# heaters-sensors.net
KiCad netlist of a schematic drawn in Altium Designer
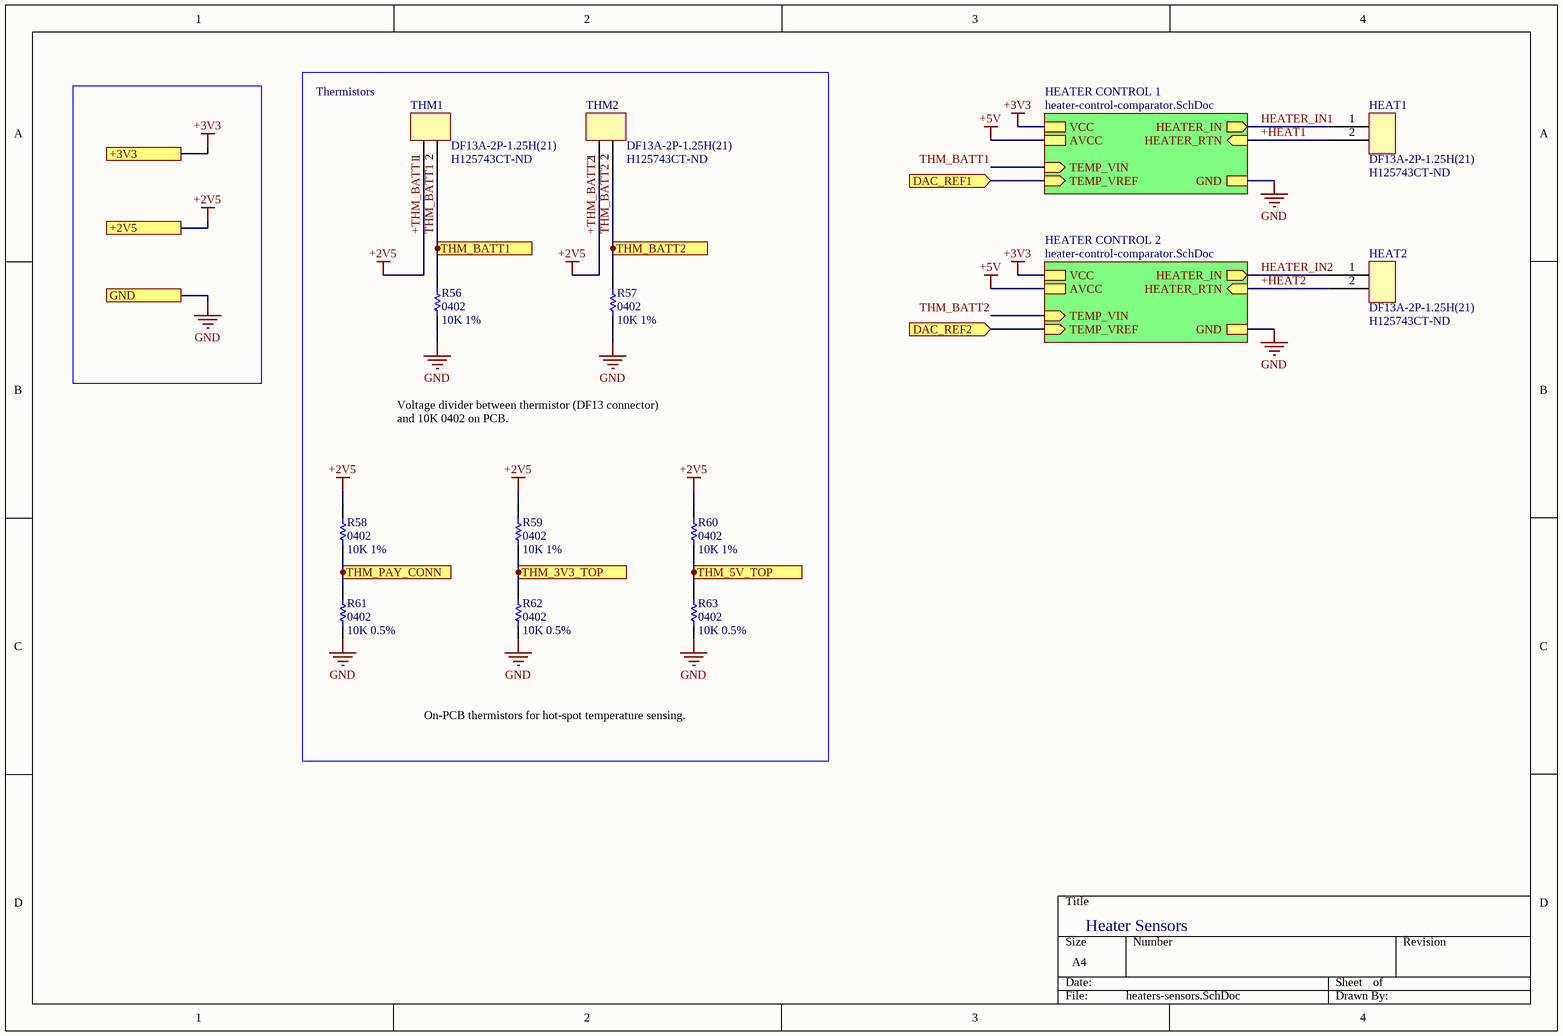
[diagram p0: heaters-sensors.SchDoc]

(export (version "E")
  (design (tool "Eeschema 10.0.6"))
  (components
    (comp (ref "HEAT1")
      (value "DF13A-2P-1.25H(21)")
      (footprint "DF13A-2P-1.25H(21)")
      (description "2 pos DF13 right angle surface mount connector")
      (fields (field (name "SUPPLIER PART NUMBER 1") "H125743CT-ND"))
      (libsource (lib "") (part "DF13A-2P-1.25H(21)_1"))
    )
    (comp (ref "HEAT2")
      (value "DF13A-2P-1.25H(21)")
      (footprint "DF13A-2P-1.25H(21)")
      (description "2 pos DF13 right angle surface mount connector")
      (fields (field (name "SUPPLIER PART NUMBER 1") "H125743CT-ND"))
      (libsource (lib "") (part "DF13A-2P-1.25H(21)_1"))
    )
    (comp (ref "R56")
      (value "0402")
      (footprint "RES0402R")
      (description "0402 resistor")
      (fields (field (name "ALTIUM_VALUE") "10K 1%"))
      (libsource (lib "heron-general") (part "RES0402"))
    )
    (comp (ref "R57")
      (value "0402")
      (footprint "RES0402R")
      (description "0402 resistor")
      (fields (field (name "ALTIUM_VALUE") "10K 1%"))
      (libsource (lib "heron-general") (part "RES0402"))
    )
    (comp (ref "R58")
      (value "0402")
      (footprint "RES0402R")
      (description "0402 resistor")
      (fields (field (name "ALTIUM_VALUE") "10K 1%"))
      (libsource (lib "heron-general") (part "RES0402"))
    )
    (comp (ref "R59")
      (value "0402")
      (footprint "RES0402R")
      (description "0402 resistor")
      (fields (field (name "ALTIUM_VALUE") "10K 1%"))
      (libsource (lib "heron-general") (part "RES0402"))
    )
    (comp (ref "R60")
      (value "0402")
      (footprint "RES0402R")
      (description "0402 resistor")
      (fields (field (name "ALTIUM_VALUE") "10K 1%"))
      (libsource (lib "heron-general") (part "RES0402"))
    )
    (comp (ref "R61")
      (value "0402")
      (footprint "RES0402R")
      (description "0402 thermistor")
      (fields (field (name "ALTIUM_VALUE") "10K 0.5%"))
      (libsource (lib "heron-general") (part "RES0402"))
    )
    (comp (ref "R62")
      (value "0402")
      (footprint "RES0402R")
      (description "0402 thermistor")
      (fields (field (name "ALTIUM_VALUE") "10K 0.5%"))
      (libsource (lib "heron-general") (part "RES0402"))
    )
    (comp (ref "R63")
      (value "0402")
      (footprint "RES0402R")
      (description "0402 thermistor")
      (fields (field (name "ALTIUM_VALUE") "10K 0.5%"))
      (libsource (lib "heron-general") (part "RES0402"))
    )
    (comp (ref "THM1")
      (value "DF13A-2P-1.25H(21)")
      (footprint "DF13A-2P-1.25H(21)")
      (description "2 pos DF13 right angle surface mount connector")
      (fields (field (name "SUPPLIER PART NUMBER 1") "H125743CT-ND"))
      (libsource (lib "heron-general") (part "DF13A-2P-1.25H(21)"))
    )
    (comp (ref "THM2")
      (value "DF13A-2P-1.25H(21)")
      (footprint "DF13A-2P-1.25H(21)")
      (description "2 pos DF13 right angle surface mount connector")
      (fields (field (name "SUPPLIER PART NUMBER 1") "H125743CT-ND"))
      (libsource (lib "heron-general") (part "DF13A-2P-1.25H(21)"))
    )
  )
  (nets
    (net (code "1") (name "+2V5") (class "Default")
      (node (ref "R58") (pin "2") (pinfunction "2_2") (pintype "passive"))
      (node (ref "R59") (pin "2") (pinfunction "2_2") (pintype "passive"))
      (node (ref "R60") (pin "2") (pinfunction "2_2") (pintype "passive"))
      (node (ref "THM1") (pin "1") (pintype "passive"))
      (node (ref "THM2") (pin "1") (pintype "passive"))
    )
    (net (code "4") (name "/+HEAT1") (class "Default") (node (ref "HEAT1") (pin "2") (pintype "passive")))
    (net (code "5") (name "/+HEAT2") (class "Default") (node (ref "HEAT2") (pin "2") (pintype "passive")))
    (net (code "8") (name "/HEATER_IN1") (class "Default") (node (ref "HEAT1") (pin "1") (pintype "passive")))
    (net (code "9") (name "/HEATER_IN2") (class "Default") (node (ref "HEAT2") (pin "1") (pintype "passive")))
    (net (code "10") (name "/THM_3V3_TOP") (class "Default")
      (node (ref "R59") (pin "1") (pinfunction "1_1") (pintype "passive"))
      (node (ref "R62") (pin "2") (pinfunction "2_2") (pintype "passive"))
    )
    (net (code "11") (name "/THM_5V_TOP") (class "Default")
      (node (ref "R60") (pin "1") (pinfunction "1_1") (pintype "passive"))
      (node (ref "R63") (pin "2") (pinfunction "2_2") (pintype "passive"))
    )
    (net (code "12") (name "/THM_BATT1") (class "Default")
      (node (ref "R56") (pin "2") (pinfunction "2_2") (pintype "passive"))
      (node (ref "THM1") (pin "2") (pintype "passive"))
    )
    (net (code "13") (name "/THM_BATT2") (class "Default")
      (node (ref "R57") (pin "2") (pinfunction "2_2") (pintype "passive"))
      (node (ref "THM2") (pin "2") (pintype "passive"))
    )
    (net (code "14") (name "/THM_PAY_CONN") (class "Default")
      (node (ref "R58") (pin "1") (pinfunction "1_1") (pintype "passive"))
      (node (ref "R61") (pin "2") (pinfunction "2_2") (pintype "passive"))
    )
    (net (code "15") (name "GND") (class "Default")
      (node (ref "R56") (pin "1") (pinfunction "1_1") (pintype "passive"))
      (node (ref "R57") (pin "1") (pinfunction "1_1") (pintype "passive"))
      (node (ref "R61") (pin "1") (pinfunction "1_1") (pintype "passive"))
      (node (ref "R62") (pin "1") (pinfunction "1_1") (pintype "passive"))
      (node (ref "R63") (pin "1") (pinfunction "1_1") (pintype "passive"))
    )
  )
)
